# USB2RS485.net
KiCad netlist of a schematic drawn in EAGLE
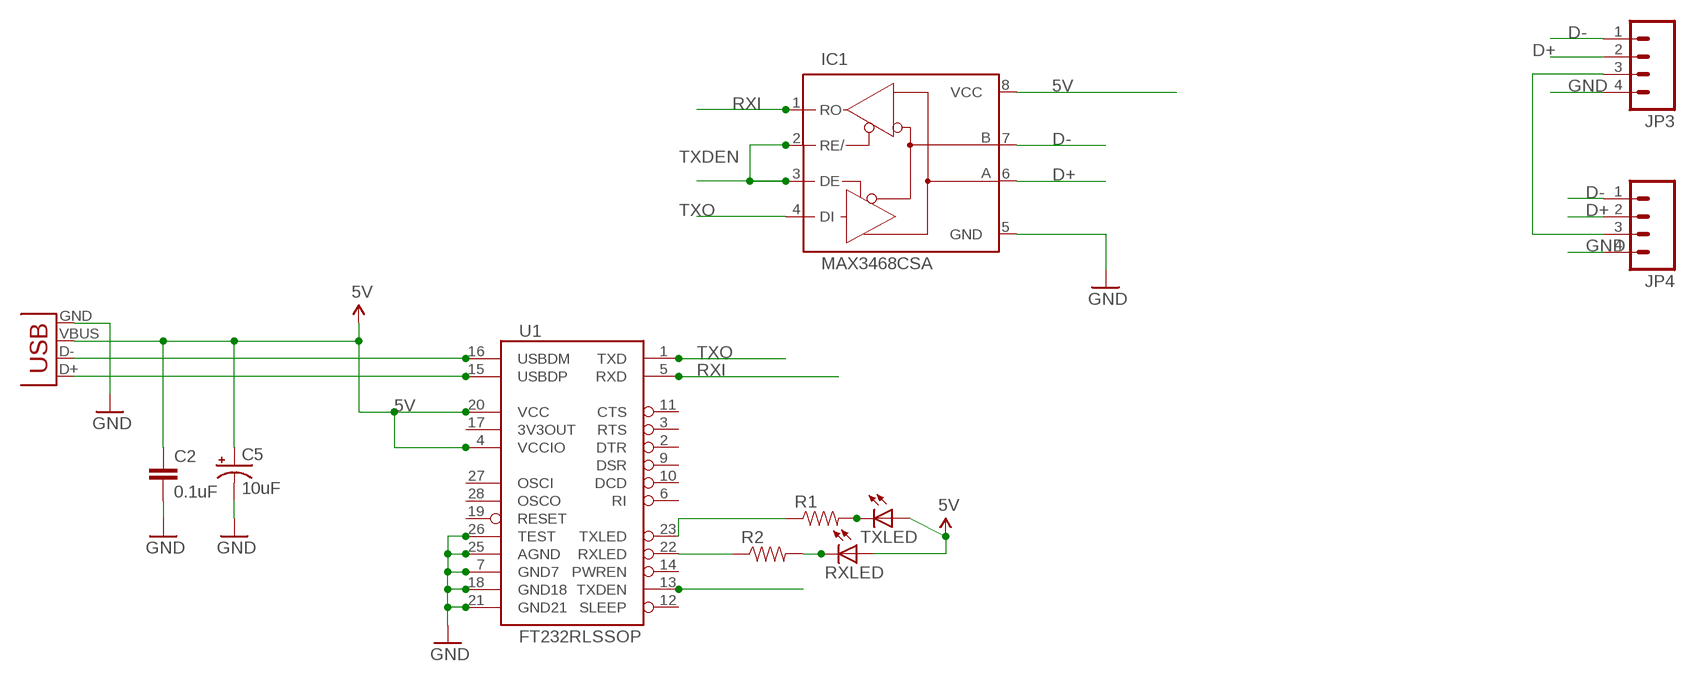
[diagram p0: schematic, sheet 1]

(export (version "E")
  (design (tool "Eeschema 10.0.6"))
  (components
    (comp (ref "C2")
      (value "0.1uF")
      (footprint "eagle-import:0402-CAP")
      (libsource (lib "eagle-import") (part "CAP0402-CAP"))
    )
    (comp (ref "C5")
      (value "10uF")
      (footprint "eagle-import:EIA3216")
      (libsource (lib "eagle-import") (part "CAP_POL1206"))
    )
    (comp (ref "IC1")
      (value "MAX3468CSA")
      (footprint "eagle-import:SO08")
      (fields (field (name "MPN") "MAX3468CSA+"))
      (libsource (lib "eagle-import") (part "MAX34SA68C"))
    )
    (comp (ref "JP3")
      (value "M04LOCK_LONGPADS")
      (footprint "eagle-import:1X04_LOCK_LONGPADS")
      (libsource (lib "eagle-import") (part "M04LOCK_LONGPADS"))
    )
    (comp (ref "JP4")
      (value "M04LOCK_LONGPADS")
      (footprint "eagle-import:1X04_LOCK_LONGPADS")
      (libsource (lib "eagle-import") (part "M04LOCK_LONGPADS"))
    )
    (comp (ref "R1")
      (value "RESISTOR0603-RES")
      (footprint "eagle-import:0603-RES")
      (libsource (lib "eagle-import") (part "RESISTOR0603-RES"))
    )
    (comp (ref "R2")
      (value "RESISTOR0603-RES")
      (footprint "eagle-import:0603-RES")
      (libsource (lib "eagle-import") (part "RESISTOR0603-RES"))
    )
    (comp (ref "RXLED")
      (value "LED0603")
      (footprint "eagle-import:LED-0603")
      (libsource (lib "eagle-import") (part "LED0603"))
    )
    (comp (ref "TXLED")
      (value "LED0603")
      (footprint "eagle-import:LED-0603")
      (libsource (lib "eagle-import") (part "LED0603"))
    )
    (comp (ref "U1")
      (value "FT232RLSSOP")
      (footprint "eagle-import:SSOP28DB")
      (libsource (lib "eagle-import") (part "FT232RLSSOP"))
    )
    (comp (ref "X2")
      (value "USB-SMD-NS")
      (footprint "eagle-import:USB-MINIB-NOSTOP")
      (libsource (lib "eagle-import") (part "USB-SMD-NS"))
    )
  )
  (nets
    (net (code "1") (name "/D+") (class "Default")
      (node (ref "IC1") (pin "6") (pinfunction "A_6") (pintype "passive"))
      (node (ref "JP3") (pin "2") (pinfunction "2_2") (pintype "passive"))
      (node (ref "JP4") (pin "2") (pinfunction "2_2") (pintype "passive"))
    )
    (net (code "2") (name "/D-") (class "Default")
      (node (ref "IC1") (pin "7") (pinfunction "B_7") (pintype "passive"))
      (node (ref "JP3") (pin "1") (pinfunction "1_1") (pintype "passive"))
      (node (ref "JP4") (pin "1") (pinfunction "1_1") (pintype "passive"))
    )
    (net (code "3") (name "/RXI") (class "Default")
      (node (ref "IC1") (pin "1") (pinfunction "RO_1") (pintype "output"))
      (node (ref "U1") (pin "5") (pinfunction "RXD_5") (pintype "input"))
    )
    (net (code "4") (name "/TXDEN") (class "Default")
      (node (ref "IC1") (pin "2") (pinfunction "RE/_2") (pintype "input"))
      (node (ref "IC1") (pin "3") (pinfunction "DE_3") (pintype "input"))
      (node (ref "U1") (pin "13") (pinfunction "TXDEN_13") (pintype "input"))
    )
    (net (code "5") (name "/TXO") (class "Default")
      (node (ref "IC1") (pin "4") (pinfunction "DI_4") (pintype "input"))
      (node (ref "U1") (pin "1") (pinfunction "TXD_1") (pintype "output"))
    )
    (net (code "6") (name "5V") (class "Default")
      (node (ref "C2") (pin "1") (pinfunction "1_1") (pintype "passive"))
      (node (ref "C5") (pin "A") (pinfunction "+_A") (pintype "passive"))
      (node (ref "IC1") (pin "8") (pinfunction "VCC_8") (pintype "power_in"))
      (node (ref "RXLED") (pin "A") (pinfunction "A_A") (pintype "passive"))
      (node (ref "TXLED") (pin "A") (pinfunction "A_A") (pintype "passive"))
      (node (ref "U1") (pin "20") (pinfunction "VCC_20") (pintype "power_in"))
      (node (ref "U1") (pin "4") (pinfunction "VCCIO_4") (pintype "power_in"))
      (node (ref "X2") (pin "VBUS") (pinfunction "VBUS_VBUS") (pintype "bidirectional"))
    )
    (net (code "7") (name "GND") (class "Default")
      (node (ref "C2") (pin "2") (pinfunction "2_2") (pintype "passive"))
      (node (ref "C5") (pin "C") (pinfunction "-_C") (pintype "passive"))
      (node (ref "IC1") (pin "5") (pinfunction "GND_5") (pintype "power_in"))
      (node (ref "JP3") (pin "4") (pinfunction "4_4") (pintype "passive"))
      (node (ref "JP4") (pin "4") (pinfunction "4_4") (pintype "passive"))
      (node (ref "U1") (pin "18") (pinfunction "GND18_18") (pintype "power_in"))
      (node (ref "U1") (pin "21") (pinfunction "GND21_21") (pintype "power_in"))
      (node (ref "U1") (pin "25") (pinfunction "AGND_25") (pintype "power_in"))
      (node (ref "U1") (pin "26") (pinfunction "TEST_26") (pintype "input"))
      (node (ref "U1") (pin "7") (pinfunction "GND7_7") (pintype "power_in"))
      (node (ref "X2") (pin "GND") (pinfunction "GND_GND") (pintype "bidirectional"))
    )
    (net (code "8") (name "Net-(JP3-Pad3)") (class "Default")
      (node (ref "JP3") (pin "3") (pinfunction "3_3") (pintype "passive"))
      (node (ref "JP4") (pin "3") (pinfunction "3_3") (pintype "passive"))
    )
    (net (code "9") (name "Net-(R1-Pad2)") (class "Default")
      (node (ref "R1") (pin "2") (pinfunction "2_2") (pintype "passive"))
      (node (ref "TXLED") (pin "C") (pinfunction "C_C") (pintype "passive"))
    )
    (net (code "10") (name "Net-(R2-Pad2)") (class "Default")
      (node (ref "R2") (pin "2") (pinfunction "2_2") (pintype "passive"))
      (node (ref "RXLED") (pin "C") (pinfunction "C_C") (pintype "passive"))
    )
    (net (code "11") (name "Net-(U1-RXLED)") (class "Default")
      (node (ref "R2") (pin "1") (pinfunction "1_1") (pintype "passive"))
      (node (ref "U1") (pin "22") (pinfunction "RXLED_22") (pintype "input"))
    )
    (net (code "12") (name "Net-(U1-TXLED)") (class "Default")
      (node (ref "R1") (pin "1") (pinfunction "1_1") (pintype "passive"))
      (node (ref "U1") (pin "23") (pinfunction "TXLED_23") (pintype "input"))
    )
    (net (code "13") (name "Net-(U1-USBDM)") (class "Default")
      (node (ref "U1") (pin "16") (pinfunction "USBDM_16") (pintype "bidirectional"))
      (node (ref "X2") (pin "D-") (pinfunction "D-_D-") (pintype "bidirectional"))
    )
    (net (code "14") (name "Net-(U1-USBDP)") (class "Default")
      (node (ref "U1") (pin "15") (pinfunction "USBDP_15") (pintype "bidirectional"))
      (node (ref "X2") (pin "D+") (pinfunction "D+_D+") (pintype "bidirectional"))
    )
    (net (code "15") (name "unconnected-(U1-3V3OUT-Pad17)") (class "Default")
      (node (ref "U1") (pin "17") (pinfunction "3V3OUT_17") (pintype "output"))
    )
    (net (code "16") (name "unconnected-(U1-CTS-Pad11)") (class "Default")
      (node (ref "U1") (pin "11") (pinfunction "CTS_11") (pintype "input"))
    )
    (net (code "17") (name "unconnected-(U1-DCD-Pad10)") (class "Default")
      (node (ref "U1") (pin "10") (pinfunction "DCD_10") (pintype "input"))
    )
    (net (code "18") (name "unconnected-(U1-DSR-Pad9)") (class "Default")
      (node (ref "U1") (pin "9") (pinfunction "DSR_9") (pintype "input"))
    )
    (net (code "19") (name "unconnected-(U1-DTR-Pad2)") (class "Default")
      (node (ref "U1") (pin "2") (pinfunction "DTR_2") (pintype "output"))
    )
    (net (code "20") (name "unconnected-(U1-OSCI-Pad27)") (class "Default")
      (node (ref "U1") (pin "27") (pinfunction "OSCI_27") (pintype "input"))
    )
    (net (code "21") (name "unconnected-(U1-OSCO-Pad28)") (class "Default")
      (node (ref "U1") (pin "28") (pinfunction "OSCO_28") (pintype "output"))
    )
    (net (code "22") (name "unconnected-(U1-PWREN-Pad14)") (class "Default")
      (node (ref "U1") (pin "14") (pinfunction "PWREN_14") (pintype "input"))
    )
    (net (code "23") (name "unconnected-(U1-RESET-Pad19)") (class "Default")
      (node (ref "U1") (pin "19") (pinfunction "RESET_19") (pintype "input"))
    )
    (net (code "24") (name "unconnected-(U1-RI-Pad6)") (class "Default")
      (node (ref "U1") (pin "6") (pinfunction "RI_6") (pintype "input"))
    )
    (net (code "25") (name "unconnected-(U1-RTS-Pad3)") (class "Default")
      (node (ref "U1") (pin "3") (pinfunction "RTS_3") (pintype "output"))
    )
    (net (code "26") (name "unconnected-(U1-SLEEP-Pad12)") (class "Default")
      (node (ref "U1") (pin "12") (pinfunction "SLEEP_12") (pintype "input"))
    )
  )
)
